# LCD_TFT_40_Pin.net
KiCad netlist of a schematic drawn in Altium Designer
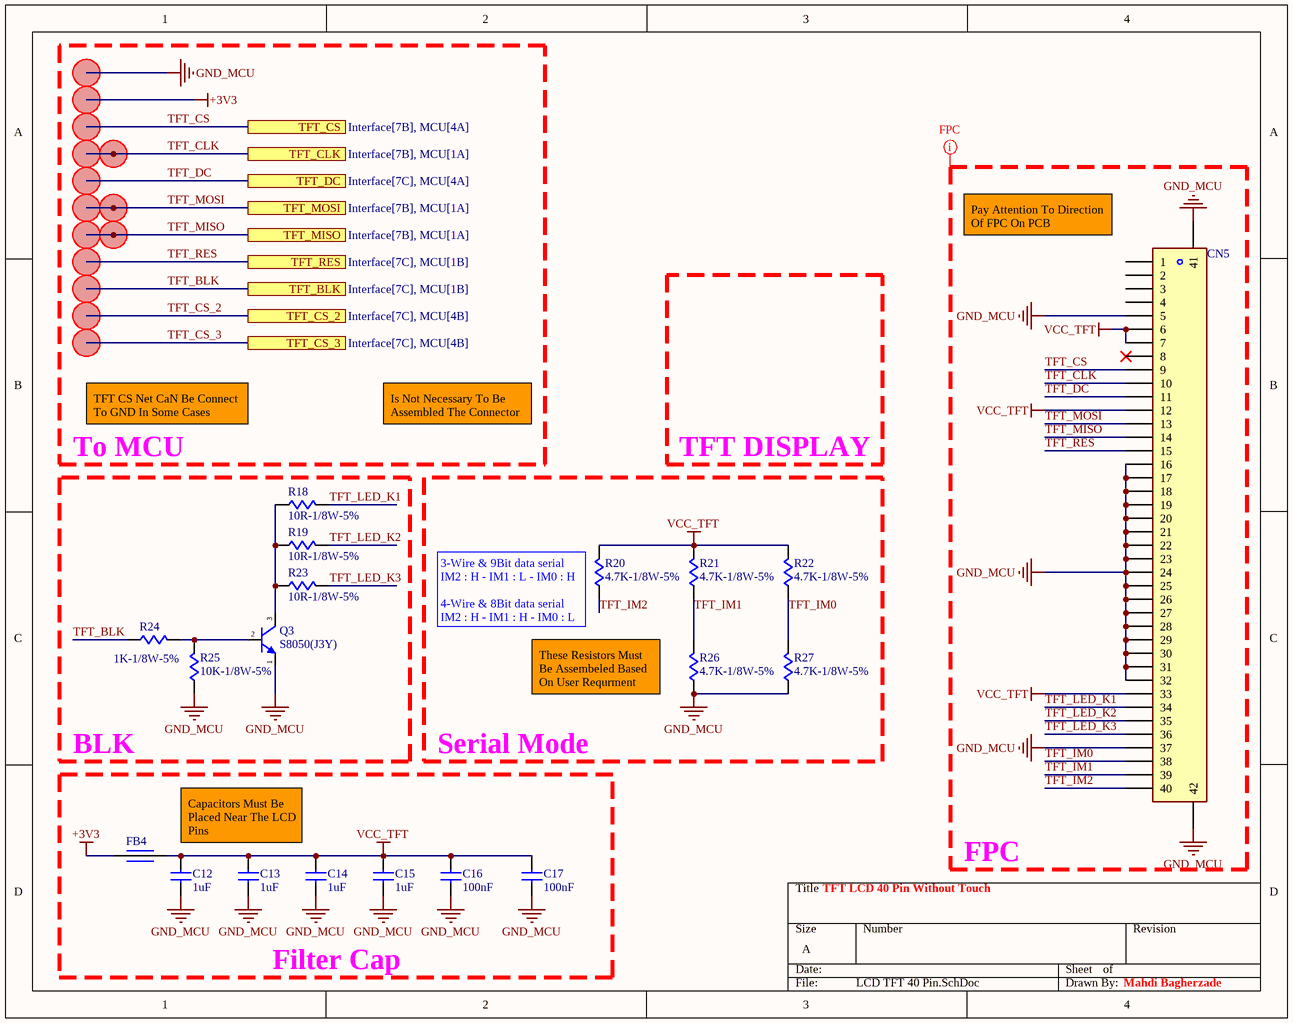
[diagram p0: LCD TFT 40 Pin.SchDoc]

(export (version "E")
  (design (tool "Eeschema 10.0.6"))
  (components
    (comp (ref "C12")
      (value "1uF")
      (footprint "C-0805")
      (description "CAPACITOR")
      (fields
        (field (name "VOLTAGE") "50V")
        (field (name "TOLERANCE") "X7R")
        (field (name "PUBLISHER") "Mahdi Bagherzadeh")
      )
      (libsource (lib "Mahdi-Bagherzadeh") (part "CAP-CER"))
    )
    (comp (ref "C13")
      (value "1uF")
      (footprint "C-0805")
      (description "CAPACITOR")
      (fields
        (field (name "VOLTAGE") "50V")
        (field (name "TOLERANCE") "X7R")
        (field (name "PUBLISHER") "Mahdi Bagherzadeh")
      )
      (libsource (lib "Mahdi-Bagherzadeh") (part "CAP-CER"))
    )
    (comp (ref "C14")
      (value "1uF")
      (footprint "C-0805")
      (description "CAPACITOR")
      (fields
        (field (name "VOLTAGE") "50V")
        (field (name "TOLERANCE") "X7R")
        (field (name "PUBLISHER") "Mahdi Bagherzadeh")
      )
      (libsource (lib "Mahdi-Bagherzadeh") (part "CAP-CER"))
    )
    (comp (ref "C15")
      (value "1uF")
      (footprint "C-0805")
      (description "CAPACITOR")
      (fields
        (field (name "VOLTAGE") "50V")
        (field (name "TOLERANCE") "X7R")
        (field (name "PUBLISHER") "Mahdi Bagherzadeh")
      )
      (libsource (lib "Mahdi-Bagherzadeh") (part "CAP-CER"))
    )
    (comp (ref "C16")
      (value "100nF")
      (footprint "C-0805")
      (description "CAPACITOR")
      (fields
        (field (name "VOLTAGE") "50V")
        (field (name "TOLERANCE") "X7R")
        (field (name "PUBLISHER") "Mahdi Bagherzadeh")
      )
      (libsource (lib "Mahdi-Bagherzadeh") (part "CAP-CER"))
    )
    (comp (ref "C17")
      (value "100nF")
      (footprint "C-0805")
      (description "CAPACITOR")
      (fields
        (field (name "VOLTAGE") "50V")
        (field (name "TOLERANCE") "X7R")
        (field (name "PUBLISHER") "Mahdi Bagherzadeh")
      )
      (libsource (lib "Mahdi-Bagherzadeh") (part "CAP-CER"))
    )
    (comp (ref "CN5")
      (value "0.5mm-Horizontal")
      (footprint "CN-FPC-40-0.5mm-hor")
      (description "CONNECTOR")
      (fields (field (name "PUBLISHER") "Mahdi Bagherzadeh"))
      (libsource (lib "Mahdi-Bagherzadeh") (part "CN-FPC-40pin"))
    )
    (comp (ref "FB4")
      (value "FERRITE BEAD")
      (footprint "FB-0805")
      (description "INDUCATOR")
      (fields (field (name "PUBLISHER") "Mahdi Bagherzadeh"))
      (libsource (lib "Mahdi-Bagherzadeh") (part "FERRITE BEAD"))
    )
    (comp (ref "Q3")
      (value "S8050(J3Y)")
      (footprint "SOT23-213")
      (description "TRANSISTOR")
      (fields (field (name "PUBLISHER") "Mahdi Bagherzadeh"))
      (libsource (lib "Mahdi-Bagherzadeh") (part "S8050"))
    )
    (comp (ref "R18")
      (value "10R-1/8W-5%")
      (footprint "R-0805")
      (description "RESISTOR")
      (fields (field (name "PUBLISHER") "Mahdi Bagherzadeh"))
      (libsource (lib "Mahdi-Bagherzadeh") (part "RES"))
    )
    (comp (ref "R19")
      (value "10R-1/8W-5%")
      (footprint "R-0805")
      (description "RESISTOR")
      (fields (field (name "PUBLISHER") "Mahdi Bagherzadeh"))
      (libsource (lib "Mahdi-Bagherzadeh") (part "RES"))
    )
    (comp (ref "R20")
      (value "4.7K-1/8W-5%")
      (footprint "R-0805")
      (description "RESISTOR")
      (fields (field (name "PUBLISHER") "Mahdi Bagherzadeh"))
      (libsource (lib "Mahdi-Bagherzadeh") (part "RES"))
    )
    (comp (ref "R21")
      (value "4.7K-1/8W-5%")
      (footprint "R-0805")
      (description "RESISTOR")
      (fields (field (name "PUBLISHER") "Mahdi Bagherzadeh"))
      (libsource (lib "Mahdi-Bagherzadeh") (part "RES"))
    )
    (comp (ref "R22")
      (value "4.7K-1/8W-5%")
      (footprint "R-0805")
      (description "RESISTOR")
      (fields (field (name "PUBLISHER") "Mahdi Bagherzadeh"))
      (libsource (lib "Mahdi-Bagherzadeh") (part "RES"))
    )
    (comp (ref "R23")
      (value "10R-1/8W-5%")
      (footprint "R-0805")
      (description "RESISTOR")
      (fields (field (name "PUBLISHER") "Mahdi Bagherzadeh"))
      (libsource (lib "Mahdi-Bagherzadeh") (part "RES"))
    )
    (comp (ref "R24")
      (value "1K-1/8W-5%")
      (footprint "R-0805")
      (description "RESISTOR")
      (fields (field (name "PUBLISHER") "Mahdi Bagherzadeh"))
      (libsource (lib "Mahdi-Bagherzadeh") (part "RES"))
    )
    (comp (ref "R25")
      (value "10K-1/8W-5%")
      (footprint "R-0805")
      (description "RESISTOR")
      (fields (field (name "PUBLISHER") "Mahdi Bagherzadeh"))
      (libsource (lib "Mahdi-Bagherzadeh") (part "RES"))
    )
    (comp (ref "R26")
      (value "4.7K-1/8W-5%")
      (footprint "R-0805")
      (description "RESISTOR")
      (fields (field (name "PUBLISHER") "Mahdi Bagherzadeh"))
      (libsource (lib "Mahdi-Bagherzadeh") (part "RES"))
    )
    (comp (ref "R27")
      (value "4.7K-1/8W-5%")
      (footprint "R-0805")
      (description "RESISTOR")
      (fields (field (name "PUBLISHER") "Mahdi Bagherzadeh"))
      (libsource (lib "Mahdi-Bagherzadeh") (part "RES"))
    )
    (comp (ref "TP1")
      (value "~")
      (footprint "TEST POINT-DIP")
      (fields (field (name "PUBLISHER") "Mahdi Bagherzadeh"))
      (libsource (lib "Mahdi-Bagherzadeh") (part "TEST PIONT"))
    )
    (comp (ref "TP2")
      (value "~")
      (footprint "TEST POINT-DIP")
      (fields (field (name "PUBLISHER") "Mahdi Bagherzadeh"))
      (libsource (lib "Mahdi-Bagherzadeh") (part "TEST PIONT"))
    )
    (comp (ref "TP3")
      (value "~")
      (footprint "TEST POINT-DIP")
      (fields (field (name "PUBLISHER") "Mahdi Bagherzadeh"))
      (libsource (lib "Mahdi-Bagherzadeh") (part "TEST PIONT"))
    )
    (comp (ref "TP4")
      (value "~")
      (footprint "TEST POINT-DIP")
      (fields (field (name "PUBLISHER") "Mahdi Bagherzadeh"))
      (libsource (lib "Mahdi-Bagherzadeh") (part "TEST PIONT"))
    )
    (comp (ref "TP5")
      (value "~")
      (footprint "TEST POINT-DIP")
      (fields (field (name "PUBLISHER") "Mahdi Bagherzadeh"))
      (libsource (lib "Mahdi-Bagherzadeh") (part "TEST PIONT"))
    )
    (comp (ref "TP6")
      (value "~")
      (footprint "TEST POINT-DIP")
      (fields (field (name "PUBLISHER") "Mahdi Bagherzadeh"))
      (libsource (lib "Mahdi-Bagherzadeh") (part "TEST PIONT"))
    )
    (comp (ref "TP7")
      (value "~")
      (footprint "TEST POINT-DIP")
      (fields (field (name "PUBLISHER") "Mahdi Bagherzadeh"))
      (libsource (lib "Mahdi-Bagherzadeh") (part "TEST PIONT"))
    )
    (comp (ref "TP8")
      (value "~")
      (footprint "TEST POINT-DIP")
      (fields (field (name "PUBLISHER") "Mahdi Bagherzadeh"))
      (libsource (lib "Mahdi-Bagherzadeh") (part "TEST PIONT"))
    )
    (comp (ref "TP9")
      (value "~")
      (footprint "TEST POINT-DIP")
      (fields (field (name "PUBLISHER") "Mahdi Bagherzadeh"))
      (libsource (lib "Mahdi-Bagherzadeh") (part "TEST PIONT"))
    )
    (comp (ref "TP10")
      (value "~")
      (footprint "TEST POINT-DIP")
      (fields (field (name "PUBLISHER") "Mahdi Bagherzadeh"))
      (libsource (lib "Mahdi-Bagherzadeh") (part "TEST PIONT"))
    )
    (comp (ref "TP11")
      (value "~")
      (footprint "TEST POINT-DIP")
      (fields (field (name "PUBLISHER") "Mahdi Bagherzadeh"))
      (libsource (lib "Mahdi-Bagherzadeh") (part "TEST PIONT"))
    )
    (comp (ref "TP12")
      (value "~")
      (footprint "TEST POINT-DIP")
      (fields (field (name "PUBLISHER") "Mahdi Bagherzadeh"))
      (libsource (lib "Mahdi-Bagherzadeh") (part "TEST PIONT"))
    )
    (comp (ref "TP13")
      (value "~")
      (footprint "TEST POINT-DIP")
      (fields (field (name "PUBLISHER") "Mahdi Bagherzadeh"))
      (libsource (lib "Mahdi-Bagherzadeh") (part "TEST PIONT"))
    )
    (comp (ref "TP14")
      (value "~")
      (footprint "TEST POINT-DIP")
      (fields (field (name "PUBLISHER") "Mahdi Bagherzadeh"))
      (libsource (lib "Mahdi-Bagherzadeh") (part "TEST PIONT"))
    )
  )
  (nets
    (net (code "1") (name "+3V3") (class "Default")
      (node (ref "FB4") (pin "1") (pinfunction "1_1") (pintype "passive"))
      (node (ref "TP2") (pin "1") (pinfunction "TP_1") (pintype "passive"))
    )
    (net (code "2") (name "/TFT_BLK") (class "Default")
      (node (ref "R24") (pin "1") (pinfunction "1_1") (pintype "passive"))
      (node (ref "TP9") (pin "1") (pinfunction "TP_1") (pintype "passive"))
    )
    (net (code "3") (name "/TFT_CLK") (class "Default")
      (node (ref "CN5") (pin "10") (pinfunction "10_10") (pintype "passive"))
      (node (ref "TP10") (pin "1") (pinfunction "TP_1") (pintype "passive"))
      (node (ref "TP4") (pin "1") (pinfunction "TP_1") (pintype "passive"))
    )
    (net (code "4") (name "/TFT_CS") (class "Default")
      (node (ref "CN5") (pin "9") (pinfunction "9_9") (pintype "passive"))
      (node (ref "TP3") (pin "1") (pinfunction "TP_1") (pintype "passive"))
    )
    (net (code "5") (name "/TFT_CS_2") (class "Default")
      (node (ref "TP13") (pin "1") (pinfunction "TP_1") (pintype "passive"))
    )
    (net (code "6") (name "/TFT_CS_3") (class "Default")
      (node (ref "TP14") (pin "1") (pinfunction "TP_1") (pintype "passive"))
    )
    (net (code "7") (name "/TFT_DC") (class "Default")
      (node (ref "CN5") (pin "11") (pinfunction "11_11") (pintype "passive"))
      (node (ref "TP5") (pin "1") (pinfunction "TP_1") (pintype "passive"))
    )
    (net (code "8") (name "/TFT_IM0") (class "Default")
      (node (ref "CN5") (pin "38") (pinfunction "38_38") (pintype "passive"))
      (node (ref "R22") (pin "1") (pinfunction "1_1") (pintype "passive"))
      (node (ref "R27") (pin "2") (pinfunction "2_2") (pintype "passive"))
    )
    (net (code "9") (name "/TFT_IM1") (class "Default")
      (node (ref "CN5") (pin "39") (pinfunction "39_39") (pintype "passive"))
      (node (ref "R21") (pin "1") (pinfunction "1_1") (pintype "passive"))
      (node (ref "R26") (pin "2") (pinfunction "2_2") (pintype "passive"))
    )
    (net (code "10") (name "/TFT_IM2") (class "Default")
      (node (ref "CN5") (pin "40") (pinfunction "40_40") (pintype "passive"))
      (node (ref "R20") (pin "1") (pinfunction "1_1") (pintype "passive"))
    )
    (net (code "11") (name "/TFT_LED_K1") (class "Default")
      (node (ref "CN5") (pin "34") (pinfunction "34_34") (pintype "passive"))
      (node (ref "R18") (pin "2") (pinfunction "2_2") (pintype "passive"))
    )
    (net (code "12") (name "/TFT_LED_K2") (class "Default")
      (node (ref "CN5") (pin "35") (pinfunction "35_35") (pintype "passive"))
      (node (ref "R19") (pin "2") (pinfunction "2_2") (pintype "passive"))
    )
    (net (code "13") (name "/TFT_LED_K3") (class "Default")
      (node (ref "CN5") (pin "36") (pinfunction "36_36") (pintype "passive"))
      (node (ref "R23") (pin "2") (pinfunction "2_2") (pintype "passive"))
    )
    (net (code "14") (name "/TFT_MISO") (class "Default")
      (node (ref "CN5") (pin "14") (pinfunction "14_14") (pintype "passive"))
      (node (ref "TP12") (pin "1") (pinfunction "TP_1") (pintype "passive"))
      (node (ref "TP7") (pin "1") (pinfunction "TP_1") (pintype "passive"))
    )
    (net (code "15") (name "/TFT_MOSI") (class "Default")
      (node (ref "CN5") (pin "13") (pinfunction "13_13") (pintype "passive"))
      (node (ref "TP11") (pin "1") (pinfunction "TP_1") (pintype "passive"))
      (node (ref "TP6") (pin "1") (pinfunction "TP_1") (pintype "passive"))
    )
    (net (code "16") (name "/TFT_RES") (class "Default")
      (node (ref "CN5") (pin "15") (pinfunction "15_15") (pintype "passive"))
      (node (ref "TP8") (pin "1") (pinfunction "TP_1") (pintype "passive"))
    )
    (net (code "17") (name "GND_MCU") (class "Default")
      (node (ref "C12") (pin "2") (pinfunction "2_2") (pintype "passive"))
      (node (ref "C13") (pin "2") (pinfunction "2_2") (pintype "passive"))
      (node (ref "C14") (pin "2") (pinfunction "2_2") (pintype "passive"))
      (node (ref "C15") (pin "2") (pinfunction "2_2") (pintype "passive"))
      (node (ref "C16") (pin "2") (pinfunction "2_2") (pintype "passive"))
      (node (ref "C17") (pin "2") (pinfunction "2_2") (pintype "passive"))
      (node (ref "CN5") (pin "16") (pinfunction "16_16") (pintype "passive"))
      (node (ref "CN5") (pin "17") (pinfunction "17_17") (pintype "passive"))
      (node (ref "CN5") (pin "18") (pinfunction "18_18") (pintype "passive"))
      (node (ref "CN5") (pin "19") (pinfunction "19_19") (pintype "passive"))
      (node (ref "CN5") (pin "20") (pinfunction "20_20") (pintype "passive"))
      (node (ref "CN5") (pin "21") (pinfunction "21_21") (pintype "passive"))
      (node (ref "CN5") (pin "22") (pinfunction "22_22") (pintype "passive"))
      (node (ref "CN5") (pin "23") (pinfunction "23_23") (pintype "passive"))
      (node (ref "CN5") (pin "24") (pinfunction "24_24") (pintype "passive"))
      (node (ref "CN5") (pin "25") (pinfunction "25_25") (pintype "passive"))
      (node (ref "CN5") (pin "26") (pinfunction "26_26") (pintype "passive"))
      (node (ref "CN5") (pin "27") (pinfunction "27_27") (pintype "passive"))
      (node (ref "CN5") (pin "28") (pinfunction "28_28") (pintype "passive"))
      (node (ref "CN5") (pin "29") (pinfunction "29_29") (pintype "passive"))
      (node (ref "CN5") (pin "30") (pinfunction "30_30") (pintype "passive"))
      (node (ref "CN5") (pin "31") (pinfunction "31_31") (pintype "passive"))
      (node (ref "CN5") (pin "32") (pinfunction "32_32") (pintype "passive"))
      (node (ref "CN5") (pin "37") (pinfunction "37_37") (pintype "passive"))
      (node (ref "CN5") (pin "41") (pinfunction "41_41") (pintype "passive"))
      (node (ref "CN5") (pin "42") (pinfunction "42_42") (pintype "passive"))
      (node (ref "CN5") (pin "5") (pinfunction "5_5") (pintype "passive"))
      (node (ref "Q3") (pin "1") (pinfunction "E_1") (pintype "passive"))
      (node (ref "R25") (pin "1") (pinfunction "1_1") (pintype "passive"))
      (node (ref "R26") (pin "1") (pinfunction "1_1") (pintype "passive"))
      (node (ref "R27") (pin "1") (pinfunction "1_1") (pintype "passive"))
      (node (ref "TP1") (pin "1") (pinfunction "TP_1") (pintype "passive"))
    )
    (net (code "18") (name "Net-(Q3-B)") (class "Default")
      (node (ref "Q3") (pin "2") (pinfunction "B_2") (pintype "passive"))
      (node (ref "R24") (pin "2") (pinfunction "2_2") (pintype "passive"))
      (node (ref "R25") (pin "2") (pinfunction "2_2") (pintype "passive"))
    )
    (net (code "19") (name "Net-(Q3-C)") (class "Default")
      (node (ref "Q3") (pin "3") (pinfunction "C_3") (pintype "passive"))
      (node (ref "R18") (pin "1") (pinfunction "1_1") (pintype "passive"))
      (node (ref "R19") (pin "1") (pinfunction "1_1") (pintype "passive"))
      (node (ref "R23") (pin "1") (pinfunction "1_1") (pintype "passive"))
    )
    (net (code "20") (name "VCC_TFT") (class "Default")
      (node (ref "C12") (pin "1") (pinfunction "1_1") (pintype "passive"))
      (node (ref "C13") (pin "1") (pinfunction "1_1") (pintype "passive"))
      (node (ref "C14") (pin "1") (pinfunction "1_1") (pintype "passive"))
      (node (ref "C15") (pin "1") (pinfunction "1_1") (pintype "passive"))
      (node (ref "C16") (pin "1") (pinfunction "1_1") (pintype "passive"))
      (node (ref "C17") (pin "1") (pinfunction "1_1") (pintype "passive"))
      (node (ref "CN5") (pin "12") (pinfunction "12_12") (pintype "passive"))
      (node (ref "CN5") (pin "33") (pinfunction "33_33") (pintype "passive"))
      (node (ref "CN5") (pin "6") (pinfunction "6_6") (pintype "passive"))
      (node (ref "CN5") (pin "7") (pinfunction "7_7") (pintype "passive"))
      (node (ref "FB4") (pin "2") (pinfunction "2_2") (pintype "passive"))
      (node (ref "R20") (pin "2") (pinfunction "2_2") (pintype "passive"))
      (node (ref "R21") (pin "2") (pinfunction "2_2") (pintype "passive"))
      (node (ref "R22") (pin "2") (pinfunction "2_2") (pintype "passive"))
    )
    (net (code "21") (name "unconnected-(CN5-Pad1)") (class "Default")
      (node (ref "CN5") (pin "1") (pinfunction "1_1") (pintype "passive"))
    )
    (net (code "22") (name "unconnected-(CN5-Pad2)") (class "Default")
      (node (ref "CN5") (pin "2") (pinfunction "2_2") (pintype "passive"))
    )
    (net (code "23") (name "unconnected-(CN5-Pad3)") (class "Default")
      (node (ref "CN5") (pin "3") (pinfunction "3_3") (pintype "passive"))
    )
    (net (code "24") (name "unconnected-(CN5-Pad4)") (class "Default")
      (node (ref "CN5") (pin "4") (pinfunction "4_4") (pintype "passive"))
    )
    (net (code "25") (name "unconnected-(CN5-Pad8)") (class "Default")
      (node (ref "CN5") (pin "8") (pinfunction "8_8") (pintype "passive+no_connect"))
    )
  )
)
